# Face_InBack1V0.net
KiCad netlist of a schematic drawn in Altium Designer
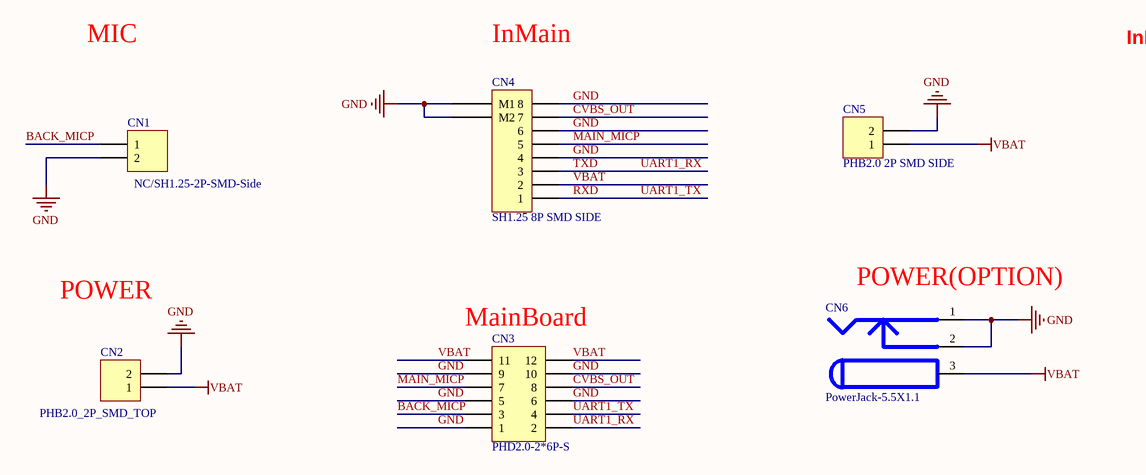
[diagram p0: Face_InBack1V0.SchDoc]

(export (version "E")
  (design (tool "Eeschema 10.0.6"))
  (components
    (comp (ref "CN1")
      (value "NC/SH1.25-2P-SMD-Side")
      (footprint "SH1.25_2P_SMD_SIDE")
      (description "SH1.25-2P-SMD-Side")
      (libsource (lib "") (part "Header2_1"))
    )
    (comp (ref "CN2")
      (value "PHB2.0_2P_SMD_TOP")
      (footprint "PH2.0_2P_SMD_TOP")
      (description "XH2.54-2P-SMD-Top, 带扣")
      (libsource (lib "LM") (part "Header2"))
    )
    (comp (ref "CN3")
      (value "PHD2.0-2*6P-S")
      (footprint "PHD2.0-2*6P-S")
      (fields (field (name "ALTIUM_UNNAMED_1") "PHD2.0-2*6P-S"))
      (libsource (lib "FCL2Back_1v3") (part "PHD 2*6P"))
    )
    (comp (ref "CN4")
      (value "SH1.25 8P SMD SIDE")
      (footprint "SH1.25_8P_SMD_SIDE")
      (description "FPC8_0.5")
      (fields (field (name "PUBLISHER") "Altium Limited"))
      (libsource (lib "S6X_1V0") (part "Header 8"))
    )
    (comp (ref "CN5")
      (value "PHB2.0 2P SMD SIDE")
      (footprint "PH2.0_2P_SMD_SIDE")
      (description "PHB2.0 2P 90")
      (fields (field (name "PUBLISHER") "Altium Limited"))
      (libsource (lib "Miscellaneous Connectors") (part "Header 2"))
    )
    (comp (ref "CN6")
      (value "PowerJack-5.5X1.1")
      (footprint "POWER_CONNECT5.5X2.1")
      (description "IC")
      (fields (field (name "ALTIUM_UNNAMED_1") "PowerJack-5.5X1.1"))
      (libsource (lib "ShenYang SCH Library 2.0") (part "PowerJack-5.5X1.1"))
    )
  )
  (nets
    (net (code "1") (name "/BACK_MICP") (class "Default")
      (node (ref "CN1") (pin "1") (pinfunction "1_1") (pintype "passive"))
      (node (ref "CN3") (pin "3") (pinfunction "3_3") (pintype "passive"))
    )
    (net (code "2") (name "/CVBS_OUT") (class "Default")
      (node (ref "CN3") (pin "8") (pinfunction "8_8") (pintype "passive"))
      (node (ref "CN4") (pin "7") (pinfunction "7_7") (pintype "passive"))
    )
    (net (code "3") (name "/MAIN_MICP") (class "Default")
      (node (ref "CN3") (pin "7") (pinfunction "7_7") (pintype "passive"))
      (node (ref "CN4") (pin "5") (pinfunction "5_5") (pintype "passive"))
    )
    (net (code "4") (name "/RXD") (class "Default")
      (node (ref "CN3") (pin "4") (pinfunction "4_4") (pintype "passive"))
      (node (ref "CN4") (pin "1") (pinfunction "1_1") (pintype "passive"))
    )
    (net (code "5") (name "/TXD") (class "Default")
      (node (ref "CN3") (pin "2") (pinfunction "2_2") (pintype "passive"))
      (node (ref "CN4") (pin "3") (pinfunction "3_3") (pintype "passive"))
    )
    (net (code "6") (name "GND") (class "Default")
      (node (ref "CN1") (pin "2") (pinfunction "2_2") (pintype "passive"))
      (node (ref "CN2") (pin "2") (pinfunction "2_2") (pintype "passive"))
      (node (ref "CN3") (pin "1") (pinfunction "1_1") (pintype "passive"))
      (node (ref "CN3") (pin "10") (pinfunction "10_10") (pintype "passive"))
      (node (ref "CN3") (pin "5") (pinfunction "5_5") (pintype "passive"))
      (node (ref "CN3") (pin "6") (pinfunction "6_6") (pintype "passive"))
      (node (ref "CN3") (pin "9") (pinfunction "9_9") (pintype "passive"))
      (node (ref "CN4") (pin "4") (pinfunction "4_4") (pintype "passive"))
      (node (ref "CN4") (pin "6") (pinfunction "6_6") (pintype "passive"))
      (node (ref "CN4") (pin "8") (pinfunction "8_8") (pintype "passive"))
      (node (ref "CN4") (pin "M1") (pinfunction "M1_M1") (pintype "passive"))
      (node (ref "CN4") (pin "M2") (pinfunction "M2_M2") (pintype "passive"))
      (node (ref "CN5") (pin "2") (pinfunction "2_2") (pintype "passive"))
      (node (ref "CN6") (pin "1") (pinfunction "1_1") (pintype "passive"))
      (node (ref "CN6") (pin "2") (pinfunction "2_2") (pintype "passive"))
    )
    (net (code "7") (name "VBAT") (class "Default")
      (node (ref "CN2") (pin "1") (pinfunction "1_1") (pintype "passive"))
      (node (ref "CN3") (pin "11") (pinfunction "11_11") (pintype "passive"))
      (node (ref "CN3") (pin "12") (pinfunction "12_12") (pintype "passive"))
      (node (ref "CN4") (pin "2") (pinfunction "2_2") (pintype "passive"))
      (node (ref "CN5") (pin "1") (pinfunction "1_1") (pintype "passive"))
      (node (ref "CN6") (pin "3") (pinfunction "3_3") (pintype "passive"))
    )
  )
)
